# schematic.net
KiCad netlist of a schematic drawn in EasyEDA
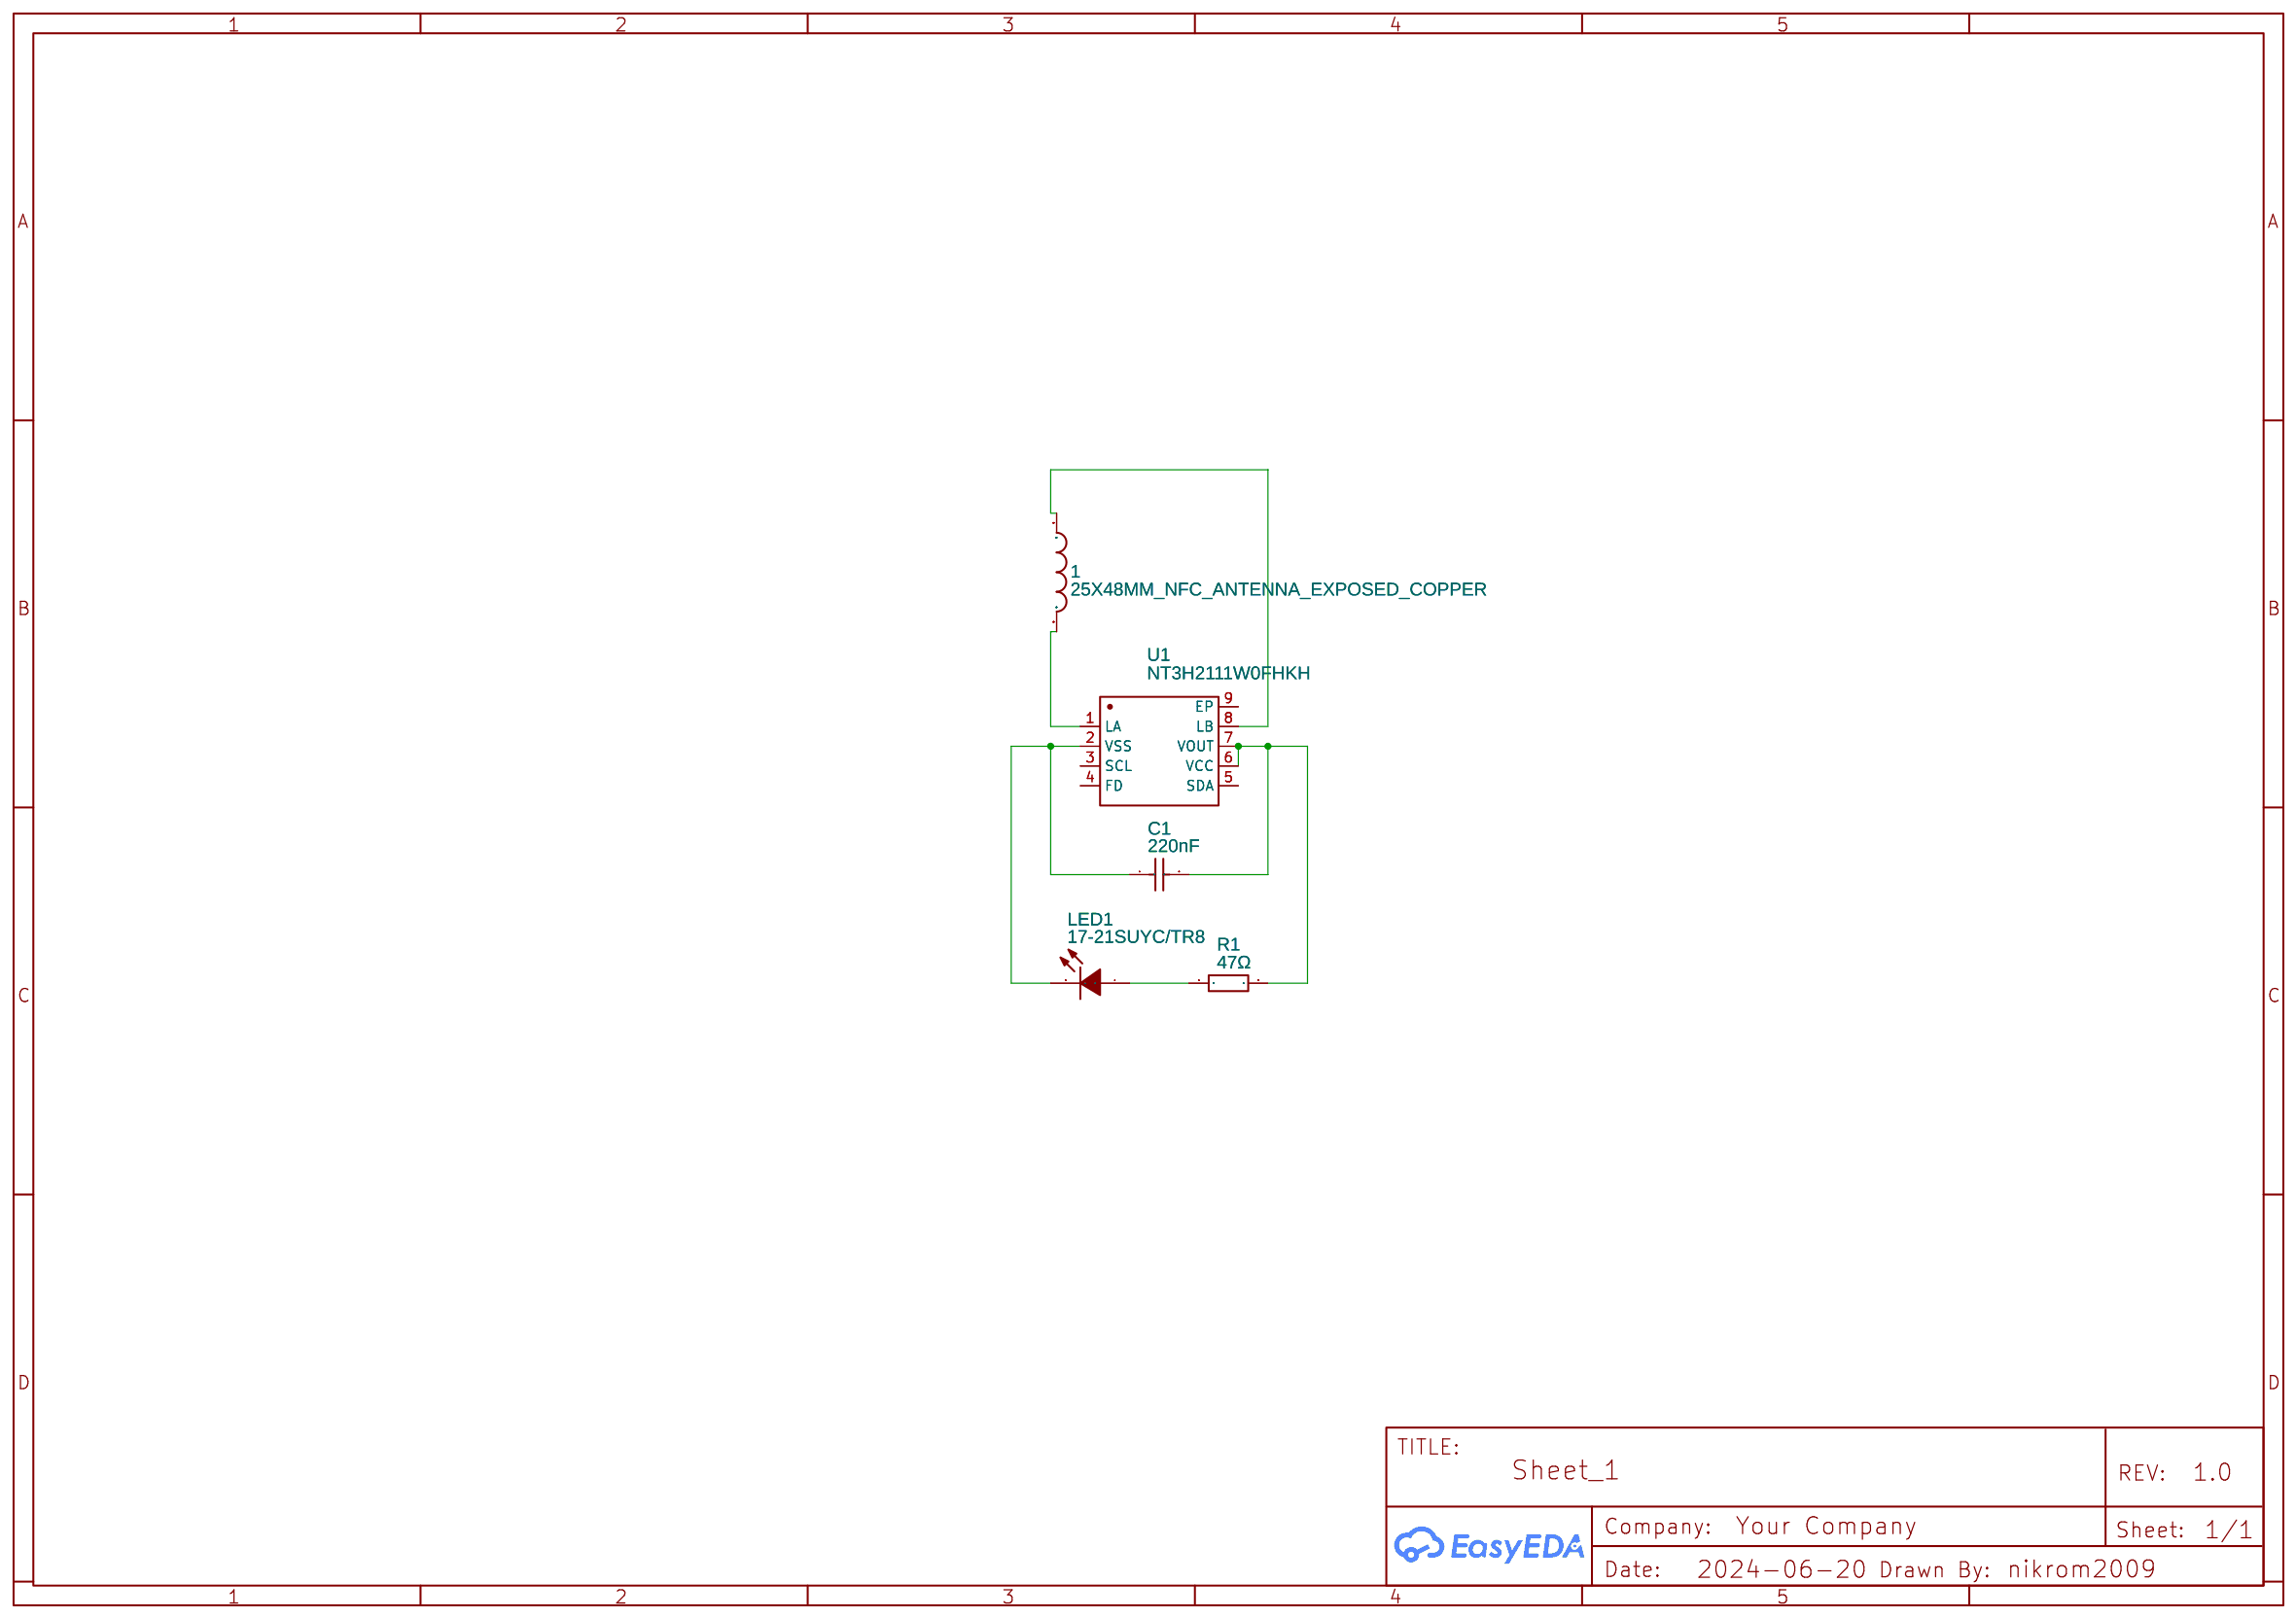
[diagram p0: schematic sheet]

(export (version "E")
  (design (tool "Eeschema 10.0.6"))
  (components
    (comp (ref "1")
      (value "25X48MM_NFC_ANTENNA_EXPOSED_COPPER")
      (libsource (lib "") (part "25X48MM_NFC_ANTENNA_EXPOSED_COPPER"))
    )
    (comp (ref "C1")
      (value "220nF")
      (fields
        (field (name "Manufacturer Part") "CL10B224KA8NNNC")
        (field (name "Manufacturer") "SAMSUNG(三星)")
      )
      (libsource (lib "") (part "CL10B224KA8NNNC"))
    )
    (comp (ref "LED1")
      (value "17-21SUYC/TR8")
      (fields (field (name "Manufacturer Part") "KT-0805黄灯") (field (name "Manufacturer") "KENTO"))
      (libsource (lib "") (part "17-21SUYC/TR8"))
    )
    (comp (ref "R1")
      (value "47Ω")
      (fields
        (field (name "Manufacturer Part") "0603WAF470JT5E")
        (field (name "Manufacturer") "UNI-ROYAL(厚声)")
      )
      (libsource (lib "") (part "0603WAF470JT5E"))
    )
    (comp (ref "U1")
      (value "NT3H2111W0FHKH")
      (fields (field (name "Manufacturer") "NXP(恩智浦)"))
      (libsource (lib "") (part "NT3H2111W0FHKH"))
    )
  )
  (nets
    (net (code "1") (name "Net-(LED1-+)") (class "Default")
      (node (ref "LED1") (pin "1") (pinfunction "+_1") (pintype "unspecified"))
      (node (ref "R1") (pin "1") (pinfunction "1_1") (pintype "input"))
    )
    (net (code "2") (name "Net-(LED1--)") (class "Default")
      (node (ref "C1") (pin "1") (pinfunction "1_1") (pintype "input"))
      (node (ref "LED1") (pin "2") (pinfunction "-_2") (pintype "unspecified"))
      (node (ref "U1") (pin "2") (pinfunction "VSS_2") (pintype "unspecified"))
    )
    (net (code "3") (name "Net-(U1-LA)") (class "Default")
      (node (ref "1") (pin "P$2") (pinfunction "P$2_P$2") (pintype "bidirectional"))
      (node (ref "U1") (pin "1") (pinfunction "LA_1") (pintype "unspecified"))
    )
    (net (code "4") (name "Net-(U1-LB)") (class "Default")
      (node (ref "1") (pin "P$1") (pinfunction "P$1_P$1") (pintype "bidirectional"))
      (node (ref "U1") (pin "8") (pinfunction "LB_8") (pintype "unspecified"))
    )
    (net (code "5") (name "Net-(U1-VCC)") (class "Default")
      (node (ref "C1") (pin "2") (pinfunction "2_2") (pintype "input"))
      (node (ref "R1") (pin "2") (pinfunction "2_2") (pintype "input"))
      (node (ref "U1") (pin "6") (pinfunction "VCC_6") (pintype "unspecified"))
      (node (ref "U1") (pin "7") (pinfunction "VOUT_7") (pintype "unspecified"))
    )
    (net (code "6") (name "unconnected-(U1-EP-Pad9)") (class "Default")
      (node (ref "U1") (pin "9") (pinfunction "EP_9") (pintype "unspecified"))
    )
    (net (code "7") (name "unconnected-(U1-FD-Pad4)") (class "Default")
      (node (ref "U1") (pin "4") (pinfunction "FD_4") (pintype "unspecified"))
    )
    (net (code "8") (name "unconnected-(U1-SCL-Pad3)") (class "Default")
      (node (ref "U1") (pin "3") (pinfunction "SCL_3") (pintype "unspecified"))
    )
    (net (code "9") (name "unconnected-(U1-SDA-Pad5)") (class "Default")
      (node (ref "U1") (pin "5") (pinfunction "SDA_5") (pintype "unspecified"))
    )
  )
)
